# DI_modified.net
KiCad netlist of a schematic drawn in Altium Designer
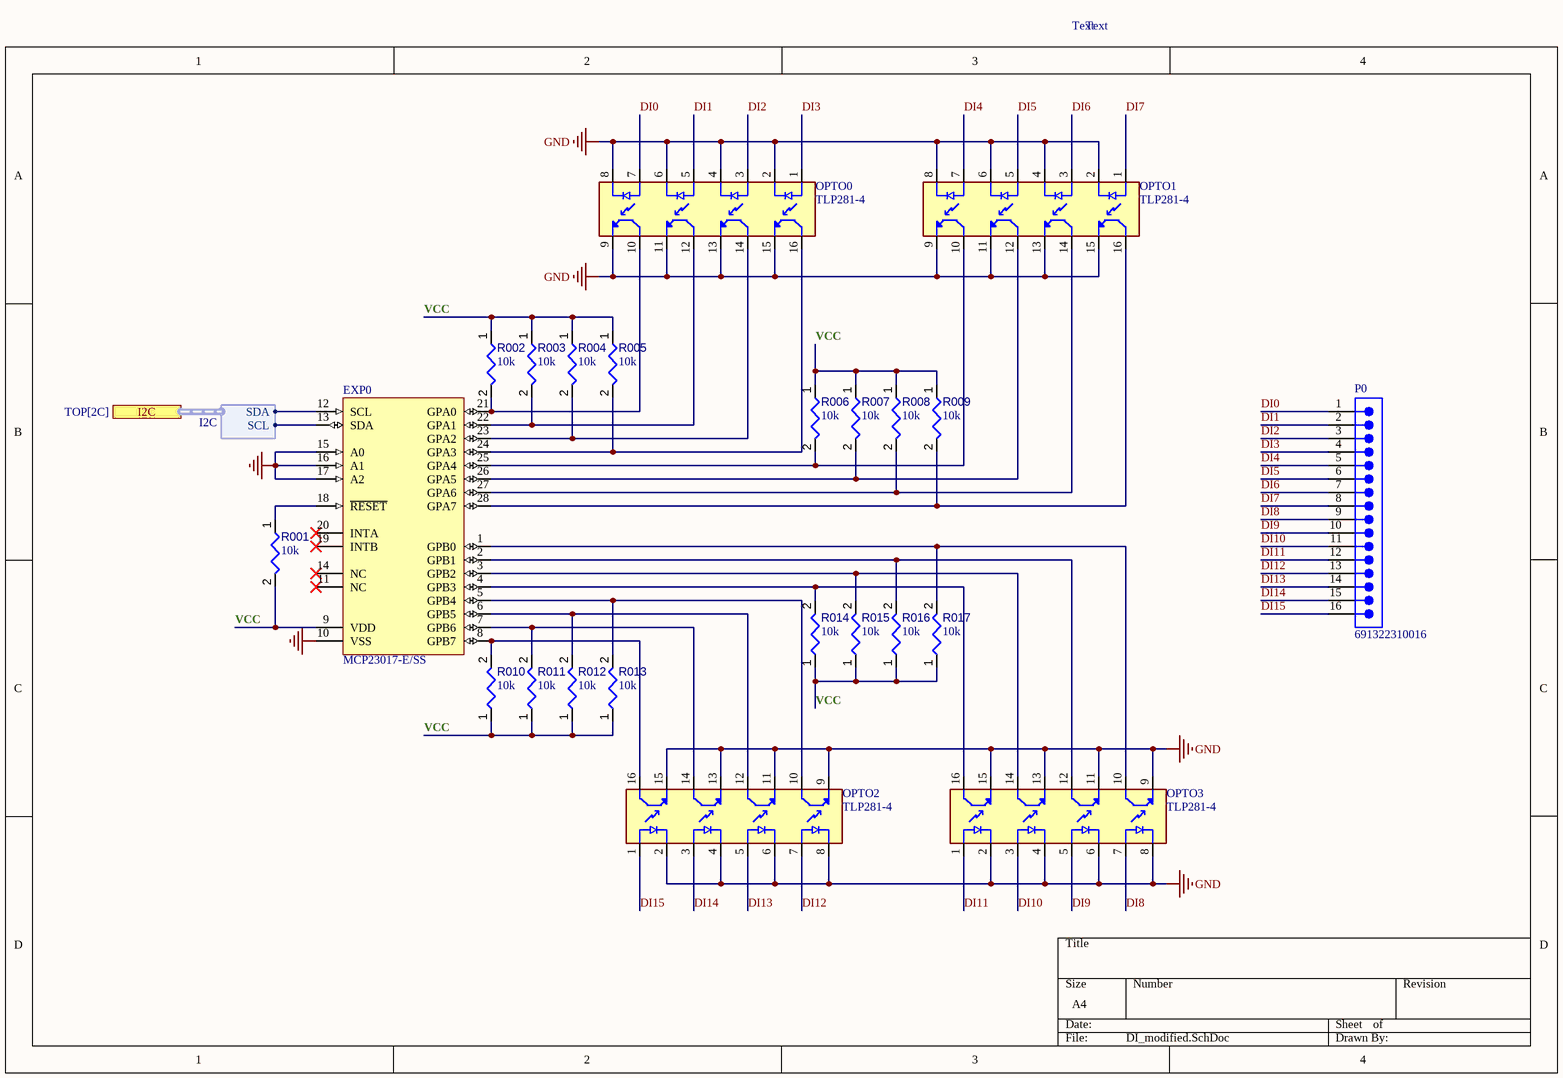
[diagram p0: DI_modified.SchDoc]

(export (version "E")
  (design (tool "Eeschema 10.0.6"))
  (components
    (comp (ref "EXP0")
      (value "MCP23017-E/SS")
      (footprint "SSOP-SS28_M")
      (description "I²C Bus IC Operating temperature: -40...+125 °C Power supply: 1.8...5.5 V Package: SSOP-20")
      (libsource (lib "HoneyPot") (part "PR-BUSIC-MCP23017-28"))
    )
    (comp (ref "OPTO0")
      (value "TLP281-4")
      (footprint "SOIC127P700X210-16N")
      (description "Optoisolator Transistor Output 2500Vrms 4 Channel 16-SOP")
      (fields (field (name "MF") "Toshiba Semiconductor"))
      (libsource (lib "HoneyPot") (part "TLP281-4"))
    )
    (comp (ref "OPTO1")
      (value "TLP281-4")
      (footprint "SOIC127P700X210-16N")
      (description "Optoisolator Transistor Output 2500Vrms 4 Channel 16-SOP")
      (fields (field (name "MF") "Toshiba Semiconductor"))
      (libsource (lib "HoneyPot") (part "TLP281-4"))
    )
    (comp (ref "OPTO2")
      (value "TLP281-4")
      (footprint "SOIC127P700X210-16N")
      (description "Optoisolator Transistor Output 2500Vrms 4 Channel 16-SOP")
      (fields (field (name "MF") "Toshiba Semiconductor"))
      (libsource (lib "HoneyPot") (part "TLP281-4"))
    )
    (comp (ref "OPTO3")
      (value "TLP281-4")
      (footprint "SOIC127P700X210-16N")
      (description "Optoisolator Transistor Output 2500Vrms 4 Channel 16-SOP")
      (fields (field (name "MF") "Toshiba Semiconductor"))
      (libsource (lib "HoneyPot") (part "TLP281-4"))
    )
    (comp (ref "P0")
      (value "691322310016")
      (footprint "691322310016")
      (description "Terminal Block, 3.81MM Pitch, Horizontal Pcb Header, 300VAC, 16 Pins")
      (libsource (lib "HoneyPot") (part "TBL - 1R - 16P - Male"))
    )
    (comp (ref "R001")
      (value "10k")
      (footprint "RESC0402(1005)_L")
      (description "10K 0.063W 1% 0402 (1005 Metric)  SMD")
      (fields (field (name "POWER") "63mW") (field (name "TOLERANCE") "1%"))
      (libsource (lib "HoneyPot") (part "10KR2F"))
    )
    (comp (ref "R002")
      (value "10k")
      (footprint "RESC1005X40X25ML05T05")
      (description "Chip Resistor, 10 KOhm, +/- 1%, 63 mW, -55 to 155 degC, 0402 (1005 Metric)")
      (fields (field (name "POWER") "63mW") (field (name "TOLERANCE") "1%"))
      (libsource (lib "HoneyPot") (part "RES-2"))
    )
    (comp (ref "R003")
      (value "10k")
      (footprint "RESC1005X40X25ML05T05")
      (description "Chip Resistor, 10 KOhm, +/- 1%, 63 mW, -55 to 155 degC, 0402 (1005 Metric)")
      (fields (field (name "POWER") "63mW") (field (name "TOLERANCE") "1%"))
      (libsource (lib "HoneyPot") (part "RES-2"))
    )
    (comp (ref "R004")
      (value "10k")
      (footprint "RESC1005X40X25ML05T05")
      (description "Chip Resistor, 10 KOhm, +/- 1%, 63 mW, -55 to 155 degC, 0402 (1005 Metric)")
      (fields (field (name "POWER") "63mW") (field (name "TOLERANCE") "1%"))
      (libsource (lib "HoneyPot") (part "RES-2"))
    )
    (comp (ref "R005")
      (value "10k")
      (footprint "RESC1005X40X25ML05T05")
      (description "Chip Resistor, 10 KOhm, +/- 1%, 63 mW, -55 to 155 degC, 0402 (1005 Metric)")
      (fields (field (name "POWER") "63mW") (field (name "TOLERANCE") "1%"))
      (libsource (lib "HoneyPot") (part "RES-2"))
    )
    (comp (ref "R006")
      (value "10k")
      (footprint "RESC1005X40X25ML05T05")
      (description "Chip Resistor, 10 KOhm, +/- 1%, 63 mW, -55 to 155 degC, 0402 (1005 Metric)")
      (fields (field (name "POWER") "63mW") (field (name "TOLERANCE") "1%"))
      (libsource (lib "HoneyPot") (part "RES-2"))
    )
    (comp (ref "R007")
      (value "10k")
      (footprint "RESC1005X40X25ML05T05")
      (description "Chip Resistor, 10 KOhm, +/- 1%, 63 mW, -55 to 155 degC, 0402 (1005 Metric)")
      (fields (field (name "POWER") "63mW") (field (name "TOLERANCE") "1%"))
      (libsource (lib "HoneyPot") (part "RES-2"))
    )
    (comp (ref "R008")
      (value "10k")
      (footprint "RESC1005X40X25ML05T05")
      (description "Chip Resistor, 10 KOhm, +/- 1%, 63 mW, -55 to 155 degC, 0402 (1005 Metric)")
      (fields (field (name "POWER") "63mW") (field (name "TOLERANCE") "1%"))
      (libsource (lib "HoneyPot") (part "RES-2"))
    )
    (comp (ref "R009")
      (value "10k")
      (footprint "RESC1005X40X25ML05T05")
      (description "Chip Resistor, 10 KOhm, +/- 1%, 63 mW, -55 to 155 degC, 0402 (1005 Metric)")
      (fields (field (name "POWER") "63mW") (field (name "TOLERANCE") "1%"))
      (libsource (lib "HoneyPot") (part "RES-2"))
    )
    (comp (ref "R010")
      (value "10k")
      (footprint "RESC1005X40X25ML05T05")
      (description "Chip Resistor, 10 KOhm, +/- 1%, 63 mW, -55 to 155 degC, 0402 (1005 Metric)")
      (fields (field (name "POWER") "63mW") (field (name "TOLERANCE") "1%"))
      (libsource (lib "HoneyPot") (part "RES-2"))
    )
    (comp (ref "R011")
      (value "10k")
      (footprint "RESC1005X40X25ML05T05")
      (description "Chip Resistor, 10 KOhm, +/- 1%, 63 mW, -55 to 155 degC, 0402 (1005 Metric)")
      (fields (field (name "POWER") "63mW") (field (name "TOLERANCE") "1%"))
      (libsource (lib "HoneyPot") (part "RES-2"))
    )
    (comp (ref "R012")
      (value "10k")
      (footprint "RESC1005X40X25ML05T05")
      (description "Chip Resistor, 10 KOhm, +/- 1%, 63 mW, -55 to 155 degC, 0402 (1005 Metric)")
      (fields (field (name "POWER") "63mW") (field (name "TOLERANCE") "1%"))
      (libsource (lib "HoneyPot") (part "RES-2"))
    )
    (comp (ref "R013")
      (value "10k")
      (footprint "RESC1005X40X25ML05T05")
      (description "Chip Resistor, 10 KOhm, +/- 1%, 63 mW, -55 to 155 degC, 0402 (1005 Metric)")
      (fields (field (name "POWER") "63mW") (field (name "TOLERANCE") "1%"))
      (libsource (lib "HoneyPot") (part "RES-2"))
    )
    (comp (ref "R014")
      (value "10k")
      (footprint "RESC1005X40X25ML05T05")
      (description "Chip Resistor, 10 KOhm, +/- 1%, 63 mW, -55 to 155 degC, 0402 (1005 Metric)")
      (fields (field (name "POWER") "63mW") (field (name "TOLERANCE") "1%"))
      (libsource (lib "HoneyPot") (part "RES-2"))
    )
    (comp (ref "R015")
      (value "10k")
      (footprint "RESC1005X40X25ML05T05")
      (description "Chip Resistor, 10 KOhm, +/- 1%, 63 mW, -55 to 155 degC, 0402 (1005 Metric)")
      (fields (field (name "POWER") "63mW") (field (name "TOLERANCE") "1%"))
      (libsource (lib "HoneyPot") (part "RES-2"))
    )
    (comp (ref "R016")
      (value "10k")
      (footprint "RESC1005X40X25ML05T05")
      (description "Chip Resistor, 10 KOhm, +/- 1%, 63 mW, -55 to 155 degC, 0402 (1005 Metric)")
      (fields (field (name "POWER") "63mW") (field (name "TOLERANCE") "1%"))
      (libsource (lib "HoneyPot") (part "RES-2"))
    )
    (comp (ref "R017")
      (value "10k")
      (footprint "RESC1005X40X25ML05T05")
      (description "Chip Resistor, 10 KOhm, +/- 1%, 63 mW, -55 to 155 degC, 0402 (1005 Metric)")
      (fields (field (name "POWER") "63mW") (field (name "TOLERANCE") "1%"))
      (libsource (lib "HoneyPot") (part "RES-2"))
    )
  )
  (nets
    (net (code "2") (name "/DI0") (class "Default")
      (node (ref "OPTO0") (pin "7") (pinfunction "A4_7") (pintype "passive"))
      (node (ref "P0") (pin "1") (pinfunction "1_1") (pintype "passive"))
    )
    (net (code "3") (name "/DI1") (class "Default")
      (node (ref "OPTO0") (pin "5") (pinfunction "A3_5") (pintype "passive"))
      (node (ref "P0") (pin "2") (pinfunction "2_2") (pintype "passive"))
    )
    (net (code "4") (name "/DI2") (class "Default")
      (node (ref "OPTO0") (pin "3") (pinfunction "A2_3") (pintype "passive"))
      (node (ref "P0") (pin "3") (pinfunction "3_3") (pintype "passive"))
    )
    (net (code "5") (name "/DI3") (class "Default")
      (node (ref "OPTO0") (pin "1") (pinfunction "A1_1") (pintype "passive"))
      (node (ref "P0") (pin "4") (pinfunction "4_4") (pintype "passive"))
    )
    (net (code "6") (name "/DI4") (class "Default")
      (node (ref "OPTO1") (pin "7") (pinfunction "A4_7") (pintype "passive"))
      (node (ref "P0") (pin "5") (pinfunction "5_5") (pintype "passive"))
    )
    (net (code "7") (name "/DI5") (class "Default")
      (node (ref "OPTO1") (pin "5") (pinfunction "A3_5") (pintype "passive"))
      (node (ref "P0") (pin "6") (pinfunction "6_6") (pintype "passive"))
    )
    (net (code "8") (name "/DI6") (class "Default")
      (node (ref "OPTO1") (pin "3") (pinfunction "A2_3") (pintype "passive"))
      (node (ref "P0") (pin "7") (pinfunction "7_7") (pintype "passive"))
    )
    (net (code "9") (name "/DI7") (class "Default")
      (node (ref "OPTO1") (pin "1") (pinfunction "A1_1") (pintype "passive"))
      (node (ref "P0") (pin "8") (pinfunction "8_8") (pintype "passive"))
    )
    (net (code "10") (name "/DI8") (class "Default")
      (node (ref "OPTO3") (pin "7") (pinfunction "A4_7") (pintype "passive"))
      (node (ref "P0") (pin "9") (pinfunction "9_9") (pintype "passive"))
    )
    (net (code "11") (name "/DI9") (class "Default")
      (node (ref "OPTO3") (pin "5") (pinfunction "A3_5") (pintype "passive"))
      (node (ref "P0") (pin "10") (pinfunction "10_10") (pintype "passive"))
    )
    (net (code "12") (name "/DI10") (class "Default")
      (node (ref "OPTO3") (pin "3") (pinfunction "A2_3") (pintype "passive"))
      (node (ref "P0") (pin "11") (pinfunction "11_11") (pintype "passive"))
    )
    (net (code "13") (name "/DI11") (class "Default")
      (node (ref "OPTO3") (pin "1") (pinfunction "A1_1") (pintype "passive"))
      (node (ref "P0") (pin "12") (pinfunction "12_12") (pintype "passive"))
    )
    (net (code "14") (name "/DI12") (class "Default")
      (node (ref "OPTO2") (pin "7") (pinfunction "A4_7") (pintype "passive"))
      (node (ref "P0") (pin "13") (pinfunction "13_13") (pintype "passive"))
    )
    (net (code "15") (name "/DI13") (class "Default")
      (node (ref "OPTO2") (pin "5") (pinfunction "A3_5") (pintype "passive"))
      (node (ref "P0") (pin "14") (pinfunction "14_14") (pintype "passive"))
    )
    (net (code "16") (name "/DI14") (class "Default")
      (node (ref "OPTO2") (pin "3") (pinfunction "A2_3") (pintype "passive"))
      (node (ref "P0") (pin "15") (pinfunction "15_15") (pintype "passive"))
    )
    (net (code "17") (name "/DI15") (class "Default")
      (node (ref "OPTO2") (pin "1") (pinfunction "A1_1") (pintype "passive"))
      (node (ref "P0") (pin "16") (pinfunction "16_16") (pintype "passive"))
    )
    (net (code "18") (name "/SCL") (class "Default")
      (node (ref "EXP0") (pin "13") (pinfunction "SDA_13") (pintype "bidirectional"))
    )
    (net (code "19") (name "/SDA") (class "Default")
      (node (ref "EXP0") (pin "12") (pinfunction "SCL_12") (pintype "input"))
    )
    (net (code "20") (name "/VCC") (class "Default")
      (node (ref "EXP0") (pin "9") (pinfunction "VDD_9") (pintype "power_in"))
      (node (ref "R001") (pin "2") (pinfunction "2_2") (pintype "passive"))
      (node (ref "R002") (pin "1") (pinfunction "1_1") (pintype "passive"))
      (node (ref "R003") (pin "1") (pinfunction "1_1") (pintype "passive"))
      (node (ref "R004") (pin "1") (pinfunction "1_1") (pintype "passive"))
      (node (ref "R005") (pin "1") (pinfunction "1_1") (pintype "passive"))
      (node (ref "R006") (pin "1") (pinfunction "1_1") (pintype "passive"))
      (node (ref "R007") (pin "1") (pinfunction "1_1") (pintype "passive"))
      (node (ref "R008") (pin "1") (pinfunction "1_1") (pintype "passive"))
      (node (ref "R009") (pin "1") (pinfunction "1_1") (pintype "passive"))
      (node (ref "R010") (pin "1") (pinfunction "1_1") (pintype "passive"))
      (node (ref "R011") (pin "1") (pinfunction "1_1") (pintype "passive"))
      (node (ref "R012") (pin "1") (pinfunction "1_1") (pintype "passive"))
      (node (ref "R013") (pin "1") (pinfunction "1_1") (pintype "passive"))
      (node (ref "R014") (pin "1") (pinfunction "1_1") (pintype "passive"))
      (node (ref "R015") (pin "1") (pinfunction "1_1") (pintype "passive"))
      (node (ref "R016") (pin "1") (pinfunction "1_1") (pintype "passive"))
      (node (ref "R017") (pin "1") (pinfunction "1_1") (pintype "passive"))
    )
    (net (code "22") (name "GND") (class "Default")
      (node (ref "EXP0") (pin "10") (pinfunction "VSS_10") (pintype "power_in"))
      (node (ref "EXP0") (pin "15") (pinfunction "A0_15") (pintype "input"))
      (node (ref "EXP0") (pin "16") (pinfunction "A1_16") (pintype "input"))
      (node (ref "EXP0") (pin "17") (pinfunction "A2_17") (pintype "input"))
      (node (ref "OPTO0") (pin "11") (pinfunction "ET3_11") (pintype "passive"))
      (node (ref "OPTO0") (pin "13") (pinfunction "ET2_13") (pintype "passive"))
      (node (ref "OPTO0") (pin "15") (pinfunction "ET1_15") (pintype "passive"))
      (node (ref "OPTO0") (pin "2") (pinfunction "C1_2") (pintype "passive"))
      (node (ref "OPTO0") (pin "4") (pinfunction "C2_4") (pintype "passive"))
      (node (ref "OPTO0") (pin "6") (pinfunction "C3_6") (pintype "passive"))
      (node (ref "OPTO0") (pin "8") (pinfunction "C4_8") (pintype "passive"))
      (node (ref "OPTO0") (pin "9") (pinfunction "ET4_9") (pintype "passive"))
      (node (ref "OPTO1") (pin "11") (pinfunction "ET3_11") (pintype "passive"))
      (node (ref "OPTO1") (pin "13") (pinfunction "ET2_13") (pintype "passive"))
      (node (ref "OPTO1") (pin "15") (pinfunction "ET1_15") (pintype "passive"))
      (node (ref "OPTO1") (pin "2") (pinfunction "C1_2") (pintype "passive"))
      (node (ref "OPTO1") (pin "4") (pinfunction "C2_4") (pintype "passive"))
      (node (ref "OPTO1") (pin "6") (pinfunction "C3_6") (pintype "passive"))
      (node (ref "OPTO1") (pin "8") (pinfunction "C4_8") (pintype "passive"))
      (node (ref "OPTO1") (pin "9") (pinfunction "ET4_9") (pintype "passive"))
      (node (ref "OPTO2") (pin "11") (pinfunction "ET3_11") (pintype "passive"))
      (node (ref "OPTO2") (pin "13") (pinfunction "ET2_13") (pintype "passive"))
      (node (ref "OPTO2") (pin "15") (pinfunction "ET1_15") (pintype "passive"))
      (node (ref "OPTO2") (pin "2") (pinfunction "C1_2") (pintype "passive"))
      (node (ref "OPTO2") (pin "4") (pinfunction "C2_4") (pintype "passive"))
      (node (ref "OPTO2") (pin "6") (pinfunction "C3_6") (pintype "passive"))
      (node (ref "OPTO2") (pin "8") (pinfunction "C4_8") (pintype "passive"))
      (node (ref "OPTO2") (pin "9") (pinfunction "ET4_9") (pintype "passive"))
      (node (ref "OPTO3") (pin "11") (pinfunction "ET3_11") (pintype "passive"))
      (node (ref "OPTO3") (pin "13") (pinfunction "ET2_13") (pintype "passive"))
      (node (ref "OPTO3") (pin "15") (pinfunction "ET1_15") (pintype "passive"))
      (node (ref "OPTO3") (pin "2") (pinfunction "C1_2") (pintype "passive"))
      (node (ref "OPTO3") (pin "4") (pinfunction "C2_4") (pintype "passive"))
      (node (ref "OPTO3") (pin "6") (pinfunction "C3_6") (pintype "passive"))
      (node (ref "OPTO3") (pin "8") (pinfunction "C4_8") (pintype "passive"))
      (node (ref "OPTO3") (pin "9") (pinfunction "ET4_9") (pintype "passive"))
    )
    (net (code "23") (name "Net-(EXP0-GPA0)") (class "Default")
      (node (ref "EXP0") (pin "21") (pinfunction "GPA0_21") (pintype "bidirectional"))
      (node (ref "OPTO0") (pin "10") (pinfunction "CT4_10") (pintype "passive"))
      (node (ref "R002") (pin "2") (pinfunction "2_2") (pintype "passive"))
    )
    (net (code "24") (name "Net-(EXP0-GPA1)") (class "Default")
      (node (ref "EXP0") (pin "22") (pinfunction "GPA1_22") (pintype "bidirectional"))
      (node (ref "OPTO0") (pin "12") (pinfunction "CT3_12") (pintype "passive"))
      (node (ref "R003") (pin "2") (pinfunction "2_2") (pintype "passive"))
    )
    (net (code "25") (name "Net-(EXP0-GPA2)") (class "Default")
      (node (ref "EXP0") (pin "23") (pinfunction "GPA2_23") (pintype "bidirectional"))
      (node (ref "OPTO0") (pin "14") (pinfunction "CT2_14") (pintype "passive"))
      (node (ref "R004") (pin "2") (pinfunction "2_2") (pintype "passive"))
    )
    (net (code "26") (name "Net-(EXP0-GPA3)") (class "Default")
      (node (ref "EXP0") (pin "24") (pinfunction "GPA3_24") (pintype "bidirectional"))
      (node (ref "OPTO0") (pin "16") (pinfunction "CT1_16") (pintype "passive"))
      (node (ref "R005") (pin "2") (pinfunction "2_2") (pintype "passive"))
    )
    (net (code "27") (name "Net-(EXP0-GPA4)") (class "Default")
      (node (ref "EXP0") (pin "25") (pinfunction "GPA4_25") (pintype "bidirectional"))
      (node (ref "OPTO1") (pin "10") (pinfunction "CT4_10") (pintype "passive"))
      (node (ref "R006") (pin "2") (pinfunction "2_2") (pintype "passive"))
    )
    (net (code "28") (name "Net-(EXP0-GPA5)") (class "Default")
      (node (ref "EXP0") (pin "26") (pinfunction "GPA5_26") (pintype "bidirectional"))
      (node (ref "OPTO1") (pin "12") (pinfunction "CT3_12") (pintype "passive"))
      (node (ref "R007") (pin "2") (pinfunction "2_2") (pintype "passive"))
    )
    (net (code "29") (name "Net-(EXP0-GPA6)") (class "Default")
      (node (ref "EXP0") (pin "27") (pinfunction "GPA6_27") (pintype "bidirectional"))
      (node (ref "OPTO1") (pin "14") (pinfunction "CT2_14") (pintype "passive"))
      (node (ref "R008") (pin "2") (pinfunction "2_2") (pintype "passive"))
    )
    (net (code "30") (name "Net-(EXP0-GPA7)") (class "Default")
      (node (ref "EXP0") (pin "28") (pinfunction "GPA7_28") (pintype "bidirectional"))
      (node (ref "OPTO1") (pin "16") (pinfunction "CT1_16") (pintype "passive"))
      (node (ref "R009") (pin "2") (pinfunction "2_2") (pintype "passive"))
    )
    (net (code "31") (name "Net-(EXP0-GPB0)") (class "Default")
      (node (ref "EXP0") (pin "1") (pinfunction "GPB0_1") (pintype "bidirectional"))
      (node (ref "OPTO3") (pin "10") (pinfunction "CT4_10") (pintype "passive"))
      (node (ref "R017") (pin "2") (pinfunction "2_2") (pintype "passive"))
    )
    (net (code "32") (name "Net-(EXP0-GPB1)") (class "Default")
      (node (ref "EXP0") (pin "2") (pinfunction "GPB1_2") (pintype "bidirectional"))
      (node (ref "OPTO3") (pin "12") (pinfunction "CT3_12") (pintype "passive"))
      (node (ref "R016") (pin "2") (pinfunction "2_2") (pintype "passive"))
    )
    (net (code "33") (name "Net-(EXP0-GPB2)") (class "Default")
      (node (ref "EXP0") (pin "3") (pinfunction "GPB2_3") (pintype "bidirectional"))
      (node (ref "OPTO3") (pin "14") (pinfunction "CT2_14") (pintype "passive"))
      (node (ref "R015") (pin "2") (pinfunction "2_2") (pintype "passive"))
    )
    (net (code "34") (name "Net-(EXP0-GPB3)") (class "Default")
      (node (ref "EXP0") (pin "4") (pinfunction "GPB3_4") (pintype "bidirectional"))
      (node (ref "OPTO3") (pin "16") (pinfunction "CT1_16") (pintype "passive"))
      (node (ref "R014") (pin "2") (pinfunction "2_2") (pintype "passive"))
    )
    (net (code "35") (name "Net-(EXP0-GPB4)") (class "Default")
      (node (ref "EXP0") (pin "5") (pinfunction "GPB4_5") (pintype "bidirectional"))
      (node (ref "OPTO2") (pin "10") (pinfunction "CT4_10") (pintype "passive"))
      (node (ref "R013") (pin "2") (pinfunction "2_2") (pintype "passive"))
    )
    (net (code "36") (name "Net-(EXP0-GPB5)") (class "Default")
      (node (ref "EXP0") (pin "6") (pinfunction "GPB5_6") (pintype "bidirectional"))
      (node (ref "OPTO2") (pin "12") (pinfunction "CT3_12") (pintype "passive"))
      (node (ref "R012") (pin "2") (pinfunction "2_2") (pintype "passive"))
    )
    (net (code "37") (name "Net-(EXP0-GPB6)") (class "Default")
      (node (ref "EXP0") (pin "7") (pinfunction "GPB6_7") (pintype "bidirectional"))
      (node (ref "OPTO2") (pin "14") (pinfunction "CT2_14") (pintype "passive"))
      (node (ref "R011") (pin "2") (pinfunction "2_2") (pintype "passive"))
    )
    (net (code "38") (name "Net-(EXP0-GPB7)") (class "Default")
      (node (ref "EXP0") (pin "8") (pinfunction "GPB7_8") (pintype "bidirectional"))
      (node (ref "OPTO2") (pin "16") (pinfunction "CT1_16") (pintype "passive"))
      (node (ref "R010") (pin "2") (pinfunction "2_2") (pintype "passive"))
    )
    (net (code "39") (name "Net-(EXP0-~{RESET})") (class "Default")
      (node (ref "EXP0") (pin "18") (pinfunction "~{RESET}_18") (pintype "input"))
      (node (ref "R001") (pin "1") (pinfunction "1_1") (pintype "passive"))
    )
    (net (code "40") (name "unconnected-(EXP0-INTA-Pad20)") (class "Default")
      (node (ref "EXP0") (pin "20") (pinfunction "INTA_20") (pintype "open_collector+no_connect"))
    )
    (net (code "41") (name "unconnected-(EXP0-INTB-Pad19)") (class "Default")
      (node (ref "EXP0") (pin "19") (pinfunction "INTB_19") (pintype "open_collector+no_connect"))
    )
    (net (code "42") (name "unconnected-(EXP0-NC-Pad11)") (class "Default")
      (node (ref "EXP0") (pin "11") (pinfunction "NC_11") (pintype "passive+no_connect"))
    )
    (net (code "43") (name "unconnected-(EXP0-NC-Pad14)") (class "Default")
      (node (ref "EXP0") (pin "14") (pinfunction "NC_14") (pintype "passive+no_connect"))
    )
  )
)
